# pcb_transformer_4x_balun.net
KiCad netlist of a schematic drawn in EAGLE
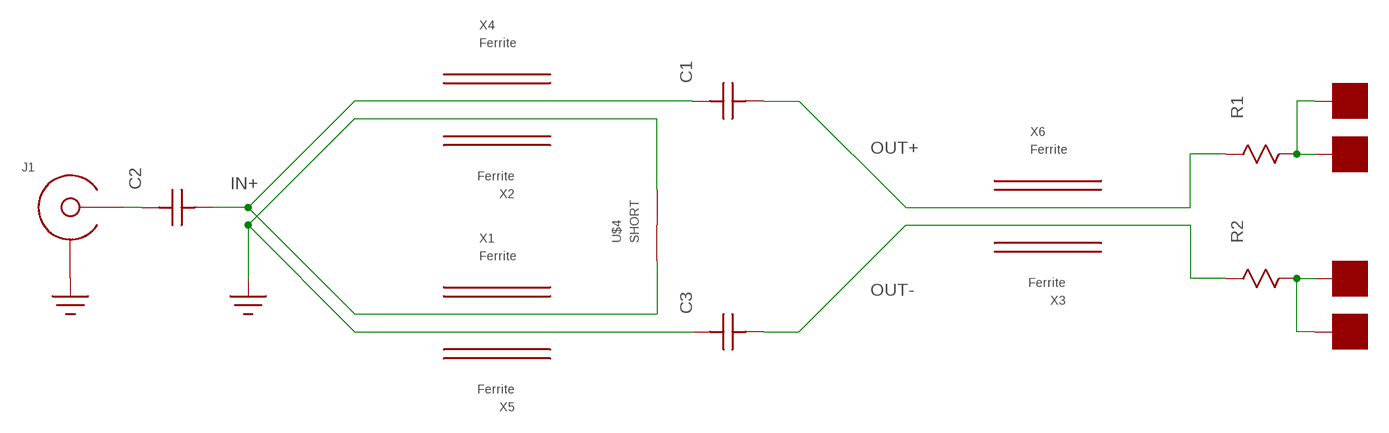
[diagram p0: schematic, sheet 1]

(export (version "E")
  (design (tool "Eeschema 10.0.6"))
  (components
    (comp (ref "C1")
      (value "C0603")
      (footprint "eagle-import:C0603")
      (libsource (lib "eagle-import") (part "C0603"))
    )
    (comp (ref "C2")
      (value "C0603")
      (footprint "eagle-import:C0603")
      (libsource (lib "eagle-import") (part "C0603"))
    )
    (comp (ref "C3")
      (value "C0603")
      (footprint "eagle-import:C0603")
      (libsource (lib "eagle-import") (part "C0603"))
    )
    (comp (ref "J1")
      (value "EDGE_LAUNCH_JACK")
      (footprint "eagle-import:EDGE_LAUNCH_RF_CON")
      (libsource (lib "eagle-import") (part "EDGE_LAUNCH_JACK"))
    )
    (comp (ref "R1")
      (value "R0603")
      (footprint "eagle-import:R0603")
      (libsource (lib "eagle-import") (part "R0603"))
    )
    (comp (ref "R2")
      (value "R0603")
      (footprint "eagle-import:R0603")
      (libsource (lib "eagle-import") (part "R0603"))
    )
    (comp (ref "U$2")
      (value "PAD50MIL")
      (footprint "eagle-import:PAD_50MIL")
      (libsource (lib "eagle-import") (part "PAD50MIL"))
    )
    (comp (ref "U$4")
      (value "SHORT")
      (footprint "eagle-import:SHORT_57MIL")
      (libsource (lib "eagle-import") (part "SHORT"))
    )
    (comp (ref "U$5")
      (value "PAD50MIL")
      (footprint "eagle-import:PAD_50MIL")
      (libsource (lib "eagle-import") (part "PAD50MIL"))
    )
    (comp (ref "U$6")
      (value "PAD50MIL")
      (footprint "eagle-import:PAD_50MIL")
      (libsource (lib "eagle-import") (part "PAD50MIL"))
    )
    (comp (ref "U$7")
      (value "PAD50MIL")
      (footprint "eagle-import:PAD_50MIL")
      (libsource (lib "eagle-import") (part "PAD50MIL"))
    )
    (comp (ref "X1")
      (value "Ferrite")
      (footprint "eagle-import:FERRITE-MP0350")
      (libsource (lib "eagle-import") (part "FERRITE_PLATE"))
    )
    (comp (ref "X2")
      (value "Ferrite")
      (footprint "eagle-import:FERRITE-MP0350")
      (libsource (lib "eagle-import") (part "FERRITE_PLATE"))
    )
    (comp (ref "X3")
      (value "Ferrite")
      (footprint "eagle-import:FERRITE-MP0350")
      (libsource (lib "eagle-import") (part "FERRITE_PLATE"))
    )
    (comp (ref "X4")
      (value "Ferrite")
      (footprint "eagle-import:FERRITE-MP0350")
      (libsource (lib "eagle-import") (part "FERRITE_PLATE"))
    )
    (comp (ref "X5")
      (value "Ferrite")
      (footprint "eagle-import:FERRITE-MP0350")
      (libsource (lib "eagle-import") (part "FERRITE_PLATE"))
    )
    (comp (ref "X6")
      (value "Ferrite")
      (footprint "eagle-import:FERRITE-MP0350")
      (libsource (lib "eagle-import") (part "FERRITE_PLATE"))
    )
  )
  (nets
    (net (code "1") (name "/IN+") (class "Default")
      (node (ref "C1") (pin "P$2") (pinfunction "P$2_P$2") (pintype "bidirectional"))
      (node (ref "C2") (pin "P$1") (pinfunction "P$1_P$1") (pintype "bidirectional"))
      (node (ref "U$4") (pin "P$1") (pinfunction "P$1_P$1") (pintype "bidirectional"))
    )
    (net (code "2") (name "/OUT+") (class "Default")
      (node (ref "C1") (pin "P$1") (pinfunction "P$1_P$1") (pintype "bidirectional"))
      (node (ref "R1") (pin "P$1") (pinfunction "P$3_P$1") (pintype "bidirectional"))
    )
    (net (code "3") (name "/OUT-") (class "Default")
      (node (ref "C3") (pin "P$1") (pinfunction "P$1_P$1") (pintype "bidirectional"))
      (node (ref "R2") (pin "P$1") (pinfunction "P$3_P$1") (pintype "bidirectional"))
    )
    (net (code "4") (name "GND") (class "Default")
      (node (ref "C3") (pin "P$2") (pinfunction "P$2_P$2") (pintype "bidirectional"))
      (node (ref "J1") (pin "GND@1") (pinfunction "SHIELD_GND@1") (pintype "bidirectional"))
      (node (ref "J1") (pin "GND@10") (pinfunction "SHIELD_GND@10") (pintype "bidirectional"))
      (node (ref "J1") (pin "GND@11") (pinfunction "SHIELD_GND@11") (pintype "bidirectional"))
      (node (ref "J1") (pin "GND@12") (pinfunction "SHIELD_GND@12") (pintype "bidirectional"))
      (node (ref "J1") (pin "GND@2") (pinfunction "SHIELD_GND@2") (pintype "bidirectional"))
      (node (ref "J1") (pin "GND@3") (pinfunction "SHIELD_GND@3") (pintype "bidirectional"))
      (node (ref "J1") (pin "GND@4") (pinfunction "SHIELD_GND@4") (pintype "bidirectional"))
      (node (ref "J1") (pin "GND@5") (pinfunction "SHIELD_GND@5") (pintype "bidirectional"))
      (node (ref "J1") (pin "GND@6") (pinfunction "SHIELD_GND@6") (pintype "bidirectional"))
      (node (ref "J1") (pin "GND@7") (pinfunction "SHIELD_GND@7") (pintype "bidirectional"))
      (node (ref "J1") (pin "GND@8") (pinfunction "SHIELD_GND@8") (pintype "bidirectional"))
      (node (ref "J1") (pin "GND@9") (pinfunction "SHIELD_GND@9") (pintype "bidirectional"))
      (node (ref "J1") (pin "SHIELD@1") (pinfunction "SHIELD_SHIELD@1") (pintype "bidirectional"))
      (node (ref "J1") (pin "SHIELD@2") (pinfunction "SHIELD_SHIELD@2") (pintype "bidirectional"))
      (node (ref "U$4") (pin "P$2") (pinfunction "P$2_P$2") (pintype "bidirectional"))
    )
    (net (code "5") (name "Net-(C2-PadP$2)") (class "Default")
      (node (ref "C2") (pin "P$2") (pinfunction "P$2_P$2") (pintype "bidirectional"))
      (node (ref "J1") (pin "CENTER") (pinfunction "CENTER_CENTER") (pintype "bidirectional"))
    )
    (net (code "6") (name "Net-(R1-P$4)") (class "Default")
      (node (ref "R1") (pin "P$2") (pinfunction "P$4_P$2") (pintype "bidirectional"))
      (node (ref "U$2") (pin "P$1") (pinfunction "P$1_P$1") (pintype "bidirectional"))
      (node (ref "U$6") (pin "P$1") (pinfunction "P$1_P$1") (pintype "bidirectional"))
    )
    (net (code "7") (name "Net-(R2-P$4)") (class "Default")
      (node (ref "R2") (pin "P$2") (pinfunction "P$4_P$2") (pintype "bidirectional"))
      (node (ref "U$5") (pin "P$1") (pinfunction "P$1_P$1") (pintype "bidirectional"))
      (node (ref "U$7") (pin "P$1") (pinfunction "P$1_P$1") (pintype "bidirectional"))
    )
  )
)
